# Interfaces.net
KiCad netlist of a schematic drawn in Altium Designer
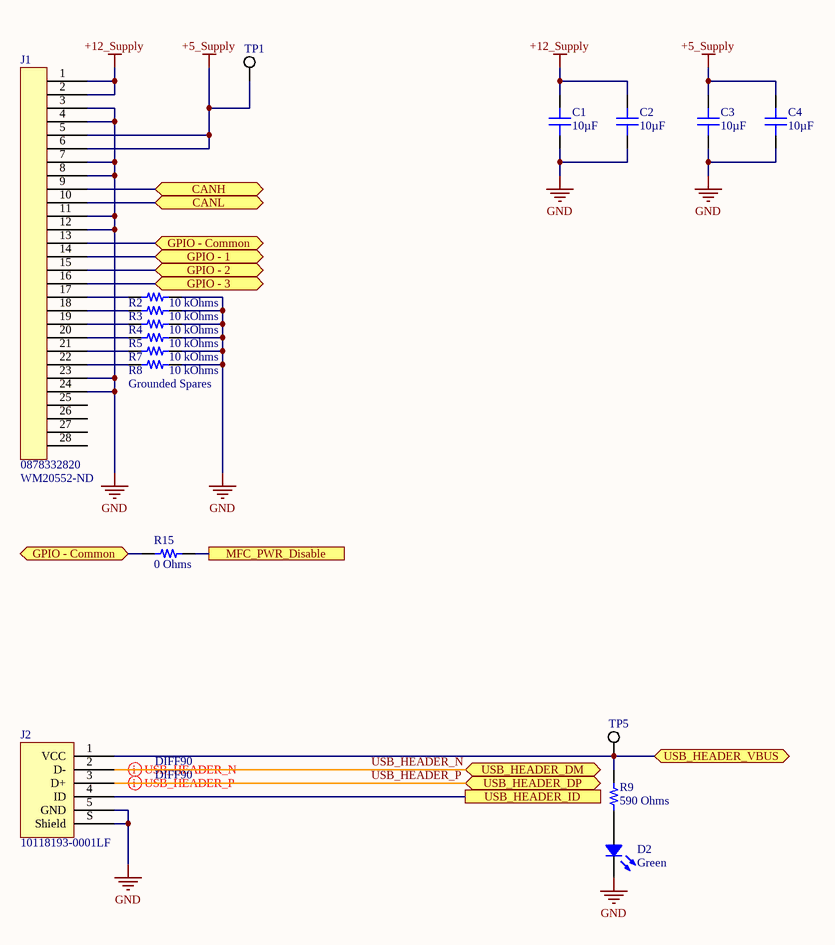
[diagram p0: Interfaces.SchDoc]

(export (version "E")
  (design (tool "Eeschema 10.0.6"))
  (components
    (comp (ref "C1")
      (value "10µF")
      (footprint "CAP 0805_2012")
      (description "CAP CER 10UF 16V X5R 0805")
      (fields (field (name "PART NUMBER") "CC0805KKX5R7BB106") (field (name "MANUFACTURER") "Yageo"))
      (libsource (lib "Celestial Altium Library - altium_library") (part "Capacitor"))
    )
    (comp (ref "C2")
      (value "10µF")
      (footprint "CAP 0805_2012")
      (description "CAP CER 10UF 16V X5R 0805")
      (fields (field (name "PART NUMBER") "CC0805KKX5R7BB106") (field (name "MANUFACTURER") "Yageo"))
      (libsource (lib "Celestial Altium Library - altium_library") (part "Capacitor"))
    )
    (comp (ref "C3")
      (value "10µF")
      (footprint "CAP 0805_2012")
      (description "CAP CER 10UF 16V X5R 0805")
      (fields (field (name "PART NUMBER") "CC0805KKX5R7BB106") (field (name "MANUFACTURER") "Yageo"))
      (libsource (lib "Celestial Altium Library - altium_library") (part "Capacitor"))
    )
    (comp (ref "C4")
      (value "10µF")
      (footprint "CAP 0805_2012")
      (description "CAP CER 10UF 16V X5R 0805")
      (fields (field (name "PART NUMBER") "CC0805KKX5R7BB106") (field (name "MANUFACTURER") "Yageo"))
      (libsource (lib "Celestial Altium Library - altium_library") (part "Capacitor"))
    )
    (comp (ref "D2")
      (value "Green")
      (footprint "LED 0603_1608 GREEN")
      (description "LED GREEN CLEAR CHIP SMD")
      (fields (field (name "PART NUMBER") "LTST-C193KGKT-5A") (field (name "MANUFACTURER") "Lite-On Inc."))
      (libsource (lib "Celestial Altium Library - altium_library") (part "LED"))
    )
    (comp (ref "J1")
      (value "0878332820")
      (footprint "0878332820")
      (fields (field (name "SUPPLIER PART NUMBER 1") "WM20552-ND"))
      (libsource (lib "HAB_Connectors") (part "0878332820"))
    )
    (comp (ref "J2")
      (value "10118193-0001LF")
      (footprint "FCI USB 10118193-0001LF")
      (description "CONN RCPT USB2.0 MICRO B SMD R/A")
      (fields (field (name "MANUFACTURER") "Amphenol ICC (FCI)"))
      (libsource (lib "Celestial Altium Library - altium_library") (part "USB 2.0 Type B Micro"))
    )
    (comp (ref "R2")
      (value "10 kOhms")
      (footprint "RES 0603_1608")
      (description "RES 10K OHM 5% 1/10W 0603")
      (fields
        (field (name "PART NUMBER") "RMCF0603JT10K0")
        (field (name "MANUFACTURER") "Stackpole Electronics Inc")
      )
      (libsource (lib "Celestial Altium Library - altium_library") (part "Resistor"))
    )
    (comp (ref "R3")
      (value "10 kOhms")
      (footprint "RES 0603_1608")
      (description "RES 10K OHM 5% 1/10W 0603")
      (fields
        (field (name "PART NUMBER") "RMCF0603JT10K0")
        (field (name "MANUFACTURER") "Stackpole Electronics Inc")
      )
      (libsource (lib "Celestial Altium Library - altium_library") (part "Resistor"))
    )
    (comp (ref "R4")
      (value "10 kOhms")
      (footprint "RES 0603_1608")
      (description "RES 10K OHM 5% 1/10W 0603")
      (fields
        (field (name "PART NUMBER") "RMCF0603JT10K0")
        (field (name "MANUFACTURER") "Stackpole Electronics Inc")
      )
      (libsource (lib "Celestial Altium Library - altium_library") (part "Resistor"))
    )
    (comp (ref "R5")
      (value "10 kOhms")
      (footprint "RES 0603_1608")
      (description "RES 10K OHM 5% 1/10W 0603")
      (fields
        (field (name "PART NUMBER") "RMCF0603JT10K0")
        (field (name "MANUFACTURER") "Stackpole Electronics Inc")
      )
      (libsource (lib "Celestial Altium Library - altium_library") (part "Resistor"))
    )
    (comp (ref "R7")
      (value "10 kOhms")
      (footprint "RES 0603_1608")
      (description "RES 10K OHM 5% 1/10W 0603")
      (fields
        (field (name "PART NUMBER") "RMCF0603JT10K0")
        (field (name "MANUFACTURER") "Stackpole Electronics Inc")
      )
      (libsource (lib "Celestial Altium Library - altium_library") (part "Resistor"))
    )
    (comp (ref "R8")
      (value "10 kOhms")
      (footprint "RES 0603_1608")
      (description "RES 10K OHM 5% 1/10W 0603")
      (fields
        (field (name "PART NUMBER") "RMCF0603JT10K0")
        (field (name "MANUFACTURER") "Stackpole Electronics Inc")
      )
      (libsource (lib "Celestial Altium Library - altium_library") (part "Resistor"))
    )
    (comp (ref "R9")
      (value "590 Ohms")
      (footprint "RES 0603_1608")
      (description "RES 590 OHM 1% 1/10W 0603")
      (fields
        (field (name "PART NUMBER") "RMCF0603FT590R")
        (field (name "MANUFACTURER") "Stackpole Electronics Inc")
      )
      (libsource (lib "Celestial Altium Library - altium_library") (part "Resistor"))
    )
    (comp (ref "R15")
      (value "0 Ohms")
      (footprint "RES 0603_1608")
      (description "RES 0 OHM JUMPER 1/10W 0603")
      (fields
        (field (name "PART NUMBER") "RMCF0603ZT0R00")
        (field (name "MANUFACTURER") "Stackpole Electronics Inc")
      )
      (libsource (lib "Celestial Altium Library - altium_library") (part "Resistor"))
    )
    (comp (ref "TP1")
      (value "5019")
      (footprint "KSTN-5019_V")
      (description "Test Point, 1 Position SMD, RoHS, Tape and Reel")
      (libsource (lib "Altium Content Vault") (part "TESTPOINT_WHITE"))
    )
    (comp (ref "TP5")
      (value "5019")
      (footprint "KSTN-5019_V")
      (description "Test Point, 1 Position SMD, RoHS, Tape and Reel")
      (libsource (lib "Altium Content Vault") (part "TESTPOINT_WHITE"))
    )
  )
  (nets
    (net (code "1") (name "+5_Supply") (class "Default")
      (node (ref "C3") (pin "2") (pinfunction "2_2") (pintype "passive"))
      (node (ref "C4") (pin "2") (pinfunction "2_2") (pintype "passive"))
      (node (ref "J1") (pin "5") (pintype "passive"))
      (node (ref "J1") (pin "6") (pintype "passive"))
      (node (ref "TP1") (pin "1") (pinfunction "1_1") (pintype "passive"))
    )
    (net (code "2") (name "+12_Supply") (class "Default")
      (node (ref "C1") (pin "2") (pinfunction "2_2") (pintype "passive"))
      (node (ref "C2") (pin "2") (pinfunction "2_2") (pintype "passive"))
      (node (ref "J1") (pin "1") (pintype "passive"))
      (node (ref "J1") (pin "2") (pintype "passive"))
    )
    (net (code "3") (name "/CANH") (class "Default") (node (ref "J1") (pin "9") (pintype "passive")))
    (net (code "4") (name "/CANL") (class "Default") (node (ref "J1") (pin "10") (pintype "passive")))
    (net (code "5") (name "/GPIO - 1") (class "Default") (node (ref "J1") (pin "14") (pintype "passive")))
    (net (code "6") (name "/GPIO - 2") (class "Default") (node (ref "J1") (pin "15") (pintype "passive")))
    (net (code "7") (name "/GPIO - 3") (class "Default") (node (ref "J1") (pin "16") (pintype "passive")))
    (net (code "8") (name "/GPIO - Common") (class "Default")
      (node (ref "J1") (pin "13") (pintype "passive"))
      (node (ref "R15") (pin "1") (pinfunction "1_1") (pintype "passive"))
    )
    (net (code "9") (name "/MFC_PWR_Disable") (class "Default")
      (node (ref "R15") (pin "2") (pinfunction "2_2") (pintype "passive"))
    )
    (net (code "10") (name "/USB_HEADER_ID") (class "Default")
      (node (ref "J2") (pin "4") (pinfunction "ID_4") (pintype "passive"))
    )
    (net (code "11") (name "/USB_HEADER_N") (class "Default")
      (node (ref "J2") (pin "2") (pinfunction "D-_2") (pintype "passive"))
    )
    (net (code "12") (name "/USB_HEADER_P") (class "Default")
      (node (ref "J2") (pin "3") (pinfunction "D+_3") (pintype "passive"))
    )
    (net (code "13") (name "/USB_HEADER_VBUS") (class "Default")
      (node (ref "J2") (pin "1") (pinfunction "VCC_1") (pintype "passive"))
      (node (ref "R9") (pin "2") (pinfunction "2_2") (pintype "passive"))
      (node (ref "TP5") (pin "1") (pinfunction "1_1") (pintype "passive"))
    )
    (net (code "14") (name "GND") (class "Default")
      (node (ref "C1") (pin "1") (pinfunction "1_1") (pintype "passive"))
      (node (ref "C2") (pin "1") (pinfunction "1_1") (pintype "passive"))
      (node (ref "C3") (pin "1") (pinfunction "1_1") (pintype "passive"))
      (node (ref "C4") (pin "1") (pinfunction "1_1") (pintype "passive"))
      (node (ref "D2") (pin "2") (pinfunction "2_2") (pintype "passive"))
      (node (ref "J1") (pin "11") (pintype "passive"))
      (node (ref "J1") (pin "12") (pintype "passive"))
      (node (ref "J1") (pin "23") (pintype "passive"))
      (node (ref "J1") (pin "24") (pintype "passive"))
      (node (ref "J1") (pin "3") (pintype "passive"))
      (node (ref "J1") (pin "4") (pintype "passive"))
      (node (ref "J1") (pin "7") (pintype "passive"))
      (node (ref "J1") (pin "8") (pintype "passive"))
      (node (ref "J2") (pin "5") (pinfunction "GND_5") (pintype "passive"))
      (node (ref "J2") (pin "S") (pinfunction "Shield_S") (pintype "passive"))
      (node (ref "R2") (pin "2") (pinfunction "2_2") (pintype "passive"))
      (node (ref "R3") (pin "2") (pinfunction "2_2") (pintype "passive"))
      (node (ref "R4") (pin "2") (pinfunction "2_2") (pintype "passive"))
      (node (ref "R5") (pin "2") (pinfunction "2_2") (pintype "passive"))
      (node (ref "R7") (pin "2") (pinfunction "2_2") (pintype "passive"))
      (node (ref "R8") (pin "2") (pinfunction "2_2") (pintype "passive"))
    )
    (net (code "15") (name "Net-(D2-Pad1)") (class "Default")
      (node (ref "D2") (pin "1") (pinfunction "1_1") (pintype "passive"))
      (node (ref "R9") (pin "1") (pinfunction "1_1") (pintype "passive"))
    )
    (net (code "16") (name "Net-(J1-Pad17)") (class "Default")
      (node (ref "J1") (pin "17") (pintype "passive"))
      (node (ref "R2") (pin "1") (pinfunction "1_1") (pintype "passive"))
    )
    (net (code "17") (name "Net-(J1-Pad18)") (class "Default")
      (node (ref "J1") (pin "18") (pintype "passive"))
      (node (ref "R3") (pin "1") (pinfunction "1_1") (pintype "passive"))
    )
    (net (code "18") (name "Net-(J1-Pad19)") (class "Default")
      (node (ref "J1") (pin "19") (pintype "passive"))
      (node (ref "R4") (pin "1") (pinfunction "1_1") (pintype "passive"))
    )
    (net (code "19") (name "Net-(J1-Pad20)") (class "Default")
      (node (ref "J1") (pin "20") (pintype "passive"))
      (node (ref "R5") (pin "1") (pinfunction "1_1") (pintype "passive"))
    )
    (net (code "20") (name "Net-(J1-Pad21)") (class "Default")
      (node (ref "J1") (pin "21") (pintype "passive"))
      (node (ref "R7") (pin "1") (pinfunction "1_1") (pintype "passive"))
    )
    (net (code "21") (name "Net-(J1-Pad22)") (class "Default")
      (node (ref "J1") (pin "22") (pintype "passive"))
      (node (ref "R8") (pin "1") (pinfunction "1_1") (pintype "passive"))
    )
    (net (code "22") (name "unconnected-(J1-Pad25)") (class "Default")
      (node (ref "J1") (pin "25") (pintype "passive"))
    )
    (net (code "23") (name "unconnected-(J1-Pad26)") (class "Default")
      (node (ref "J1") (pin "26") (pintype "passive"))
    )
    (net (code "24") (name "unconnected-(J1-Pad27)") (class "Default")
      (node (ref "J1") (pin "27") (pintype "passive"))
    )
    (net (code "25") (name "unconnected-(J1-Pad28)") (class "Default")
      (node (ref "J1") (pin "28") (pintype "passive"))
    )
  )
)
